# voltage_regulator.net
KiCad netlist of a schematic drawn in EAGLE
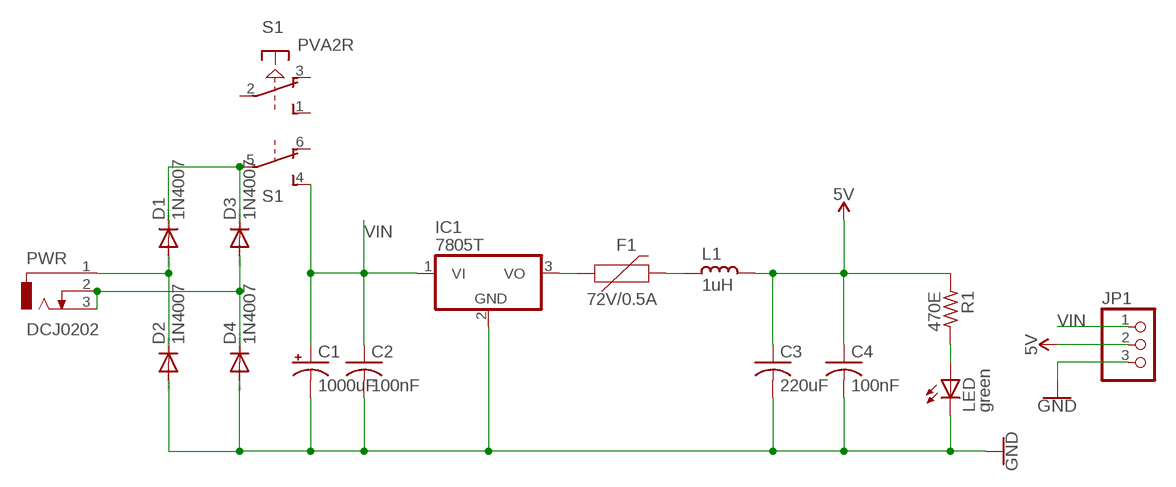
[diagram p0: schematic, sheet 1]

(export (version "E")
  (design (tool "Eeschema 10.0.6"))
  (components
    (comp (ref "C1")
      (value "1000uF")
      (footprint "eagle-import:E5-13")
      (libsource (lib "eagle-import") (part "CPOL-USE5-13"))
    )
    (comp (ref "C2")
      (value "100nF")
      (footprint "eagle-import:C0805")
      (libsource (lib "eagle-import") (part "C-USC0805"))
    )
    (comp (ref "C3")
      (value "220uF")
      (footprint "eagle-import:C0805")
      (libsource (lib "eagle-import") (part "C-USC0805"))
    )
    (comp (ref "C4")
      (value "100nF")
      (footprint "eagle-import:C0805")
      (libsource (lib "eagle-import") (part "C-USC0805"))
    )
    (comp (ref "D1")
      (value "1N4007")
      (footprint "eagle-import:DO41-10")
      (libsource (lib "eagle-import") (part "1N4004"))
    )
    (comp (ref "D2")
      (value "1N4007")
      (footprint "eagle-import:DO41-10")
      (libsource (lib "eagle-import") (part "1N4004"))
    )
    (comp (ref "D3")
      (value "1N4007")
      (footprint "eagle-import:DO41-10")
      (libsource (lib "eagle-import") (part "1N4004"))
    )
    (comp (ref "D4")
      (value "1N4007")
      (footprint "eagle-import:DO41-10")
      (libsource (lib "eagle-import") (part "1N4004"))
    )
    (comp (ref "F1")
      (value "72V/0.5A")
      (footprint "eagle-import:PTH")
      (libsource (lib "eagle-import") (part "PPTC_PTH"))
    )
    (comp (ref "IC1")
      (value "7805T")
      (footprint "eagle-import:TO220H")
      (libsource (lib "eagle-import") (part "78T05"))
    )
    (comp (ref "JP1")
      (value "PINHD-1X3")
      (footprint "eagle-import:1X03")
      (libsource (lib "eagle-import") (part "PINHD-1X3"))
    )
    (comp (ref "L1")
      (value "1uH")
      (footprint "eagle-import:L0805")
      (libsource (lib "eagle-import") (part "L_0805"))
    )
    (comp (ref "LED")
      (value "green")
      (footprint "eagle-import:CHIP-LED0805")
      (libsource (lib "eagle-import") (part "LEDCHIP-LED0805"))
    )
    (comp (ref "PWR")
      (value "DCJ0202")
      (footprint "eagle-import:DCJ0202")
      (libsource (lib "eagle-import") (part "DCJ0202"))
    )
    (comp (ref "R1")
      (value "470E")
      (footprint "eagle-import:R0805")
      (libsource (lib "eagle-import") (part "R_0805"))
    )
    (comp (ref "S1")
      (value "PVA2R")
      (footprint "eagle-import:PVA2R")
      (libsource (lib "eagle-import") (part "PVA2R"))
    )
  )
  (nets
    (net (code "1") (name "/VIN") (class "Default")
      (node (ref "C1") (pin "+") (pinfunction "+_+") (pintype "passive"))
      (node (ref "C2") (pin "1") (pinfunction "1_1") (pintype "passive"))
      (node (ref "IC1") (pin "1") (pinfunction "VI_1") (pintype "input"))
      (node (ref "JP1") (pin "1") (pinfunction "1_1") (pintype "passive"))
      (node (ref "S1") (pin "4") (pinfunction "S_4") (pintype "passive"))
    )
    (net (code "2") (name "5V") (class "Default")
      (node (ref "C3") (pin "1") (pinfunction "1_1") (pintype "passive"))
      (node (ref "C4") (pin "1") (pinfunction "1_1") (pintype "passive"))
      (node (ref "JP1") (pin "2") (pinfunction "2_2") (pintype "passive"))
      (node (ref "L1") (pin "1") (pinfunction "1_1") (pintype "passive"))
      (node (ref "R1") (pin "1") (pinfunction "1_1") (pintype "passive"))
    )
    (net (code "3") (name "GND") (class "Default")
      (node (ref "C1") (pin "-") (pinfunction "-_-") (pintype "passive"))
      (node (ref "C2") (pin "2") (pinfunction "2_2") (pintype "passive"))
      (node (ref "C3") (pin "2") (pinfunction "2_2") (pintype "passive"))
      (node (ref "C4") (pin "2") (pinfunction "2_2") (pintype "passive"))
      (node (ref "D2") (pin "A") (pinfunction "A_A") (pintype "passive"))
      (node (ref "D4") (pin "A") (pinfunction "A_A") (pintype "passive"))
      (node (ref "IC1") (pin "2") (pinfunction "GND_2") (pintype "passive"))
      (node (ref "JP1") (pin "3") (pinfunction "3_3") (pintype "passive"))
      (node (ref "LED") (pin "C") (pinfunction "C_C") (pintype "passive"))
    )
    (net (code "4") (name "Net-(D1-PadA)") (class "Default")
      (node (ref "D1") (pin "A") (pinfunction "A_A") (pintype "passive"))
      (node (ref "D2") (pin "C") (pinfunction "C_C") (pintype "passive"))
      (node (ref "PWR") (pin "1") (pinfunction "1_1") (pintype "passive"))
    )
    (net (code "5") (name "Net-(D3-PadA)") (class "Default")
      (node (ref "D3") (pin "A") (pinfunction "A_A") (pintype "passive"))
      (node (ref "D4") (pin "C") (pinfunction "C_C") (pintype "passive"))
      (node (ref "PWR") (pin "2") (pinfunction "2_2") (pintype "passive"))
      (node (ref "PWR") (pin "3") (pinfunction "3_3") (pintype "passive"))
    )
    (net (code "6") (name "Net-(F1-1)") (class "Default")
      (node (ref "F1") (pin "P$1") (pinfunction "1_P$1") (pintype "bidirectional"))
      (node (ref "IC1") (pin "3") (pinfunction "VO_3") (pintype "passive"))
    )
    (net (code "7") (name "Net-(F1-2)") (class "Default")
      (node (ref "F1") (pin "P$2") (pinfunction "2_P$2") (pintype "bidirectional"))
      (node (ref "L1") (pin "2") (pinfunction "2_2") (pintype "passive"))
    )
    (net (code "8") (name "Net-(LED-PadA)") (class "Default")
      (node (ref "LED") (pin "A") (pinfunction "A_A") (pintype "passive"))
      (node (ref "R1") (pin "2") (pinfunction "2_2") (pintype "passive"))
    )
    (net (code "9") (name "Net-(S1B-P)") (class "Default")
      (node (ref "D1") (pin "C") (pinfunction "C_C") (pintype "passive"))
      (node (ref "D3") (pin "C") (pinfunction "C_C") (pintype "passive"))
      (node (ref "S1") (pin "5") (pinfunction "P_5") (pintype "passive"))
    )
    (net (code "10") (name "unconnected-(S1A-O-Pad3)") (class "Default")
      (node (ref "S1") (pin "3") (pinfunction "O_3") (pintype "passive"))
    )
    (net (code "11") (name "unconnected-(S1A-P-Pad2)") (class "Default")
      (node (ref "S1") (pin "2") (pinfunction "P_2") (pintype "passive"))
    )
    (net (code "12") (name "unconnected-(S1A-S-Pad1)") (class "Default")
      (node (ref "S1") (pin "1") (pinfunction "S_1") (pintype "passive"))
    )
    (net (code "13") (name "unconnected-(S1B-O-Pad6)") (class "Default")
      (node (ref "S1") (pin "6") (pinfunction "O_6") (pintype "passive"))
    )
  )
)
